# W501X.net
KiCad netlist of a schematic drawn in EAGLE
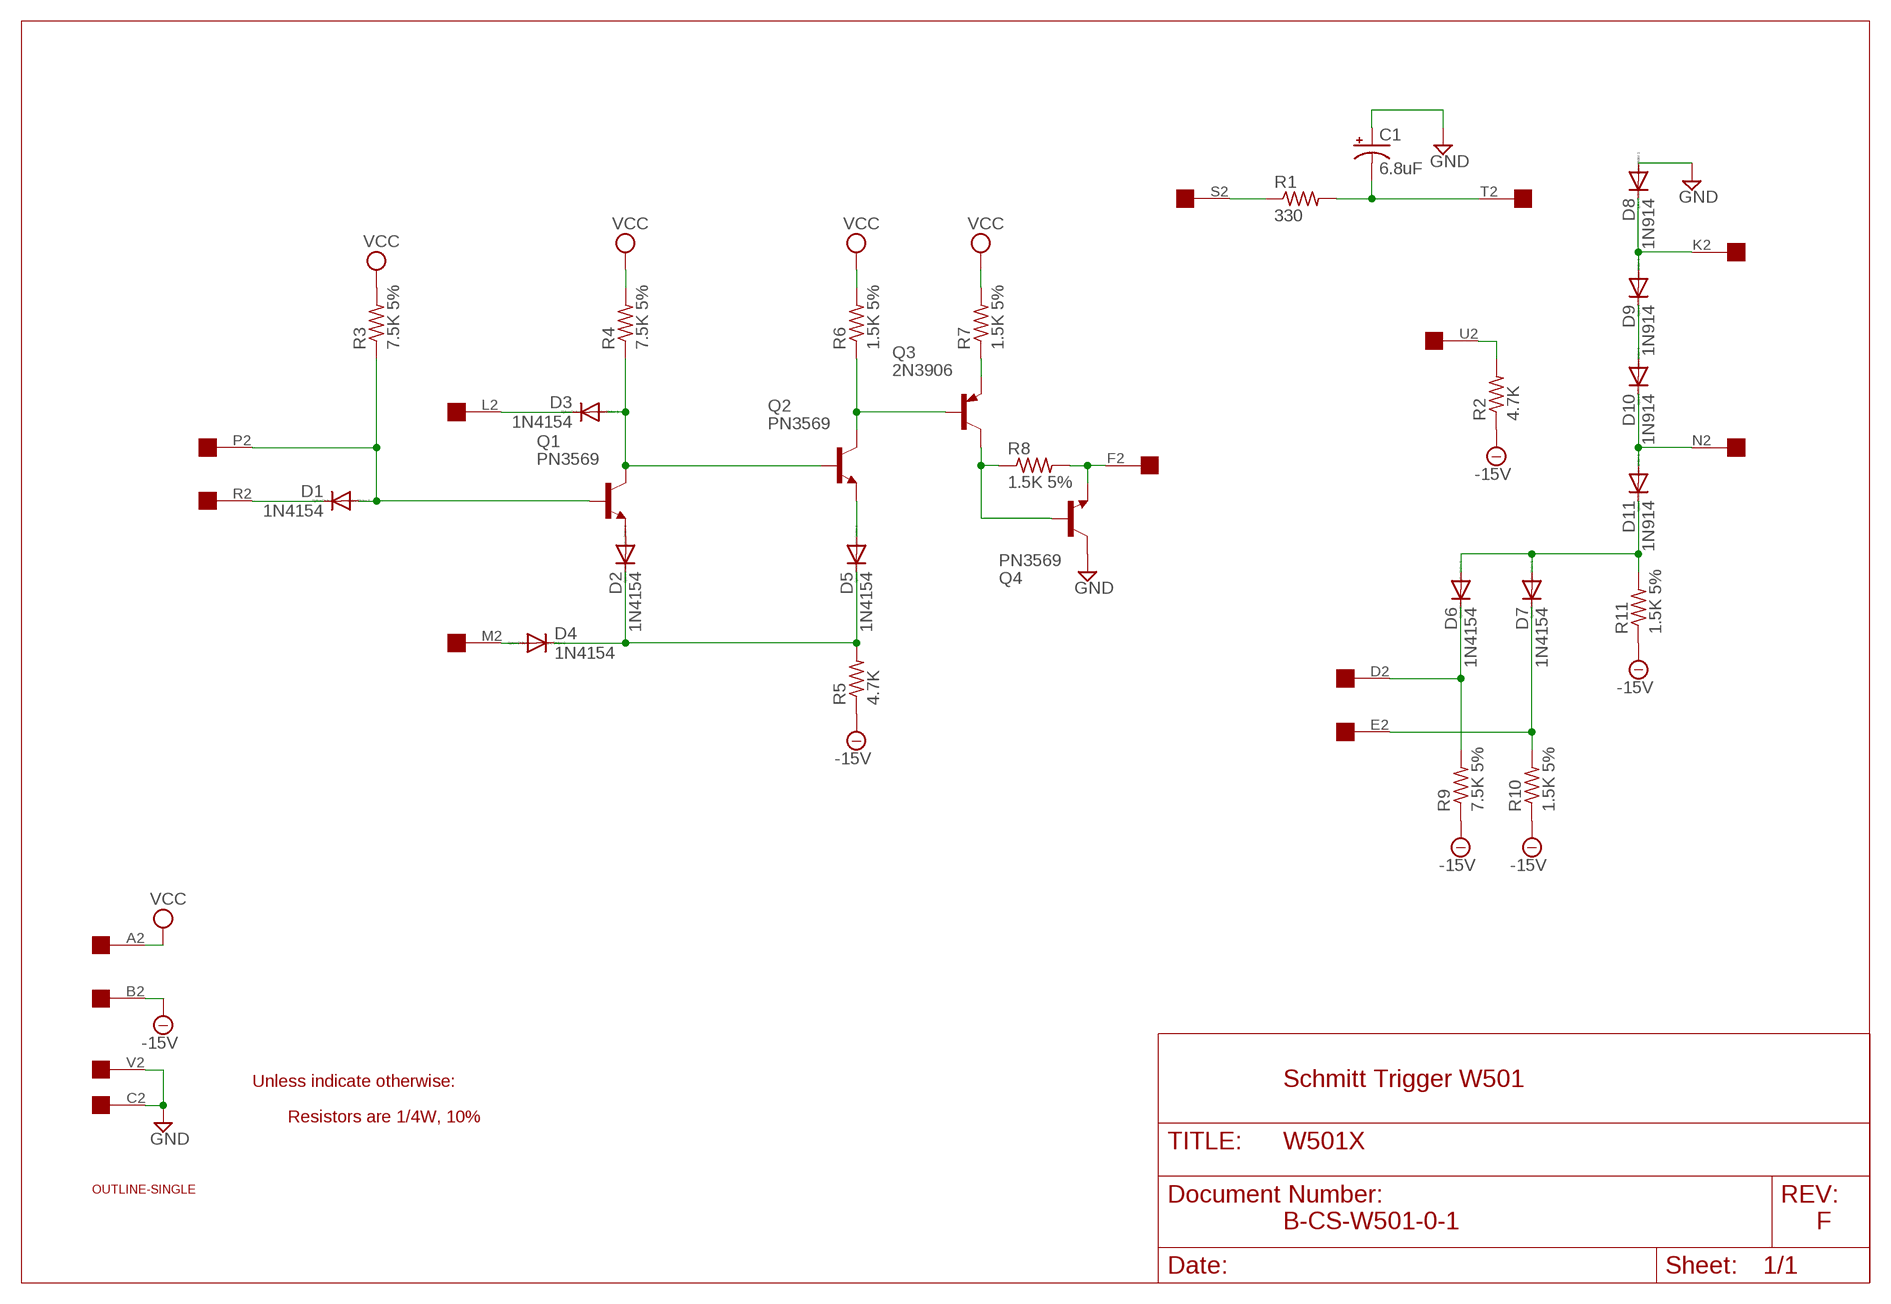
[diagram p0: schematic, sheet 1]

(export (version "E")
  (design (tool "Eeschema 10.0.6"))
  (components
    (comp (ref "C1")
      (value "6.8uF")
      (footprint "eagle-import:E15-5")
      (libsource (lib "eagle-import") (part "CPOL-USE15-5AXIAL"))
    )
    (comp (ref "D1")
      (value "1N4154")
      (footprint "eagle-import:DO35-10")
      (libsource (lib "eagle-import") (part "1N4148DO35-10"))
    )
    (comp (ref "D2")
      (value "1N4154")
      (footprint "eagle-import:DO35-10")
      (libsource (lib "eagle-import") (part "1N4148DO35-10"))
    )
    (comp (ref "D3")
      (value "1N4154")
      (footprint "eagle-import:DO35-10")
      (libsource (lib "eagle-import") (part "1N4148DO35-10"))
    )
    (comp (ref "D4")
      (value "1N4154")
      (footprint "eagle-import:DO35-10")
      (libsource (lib "eagle-import") (part "1N4148DO35-10"))
    )
    (comp (ref "D5")
      (value "1N4154")
      (footprint "eagle-import:DO35-10")
      (libsource (lib "eagle-import") (part "1N4148DO35-10"))
    )
    (comp (ref "D6")
      (value "1N4154")
      (footprint "eagle-import:DO35-10")
      (libsource (lib "eagle-import") (part "1N4148DO35-10"))
    )
    (comp (ref "D7")
      (value "1N4154")
      (footprint "eagle-import:DO35-10")
      (libsource (lib "eagle-import") (part "1N4148DO35-10"))
    )
    (comp (ref "D8")
      (value "1N914")
      (footprint "eagle-import:DO35-10")
      (libsource (lib "eagle-import") (part "1N4148DO35-10"))
    )
    (comp (ref "D9")
      (value "1N914")
      (footprint "eagle-import:DO35-10")
      (libsource (lib "eagle-import") (part "1N4148DO35-10"))
    )
    (comp (ref "D10")
      (value "1N914")
      (footprint "eagle-import:DO35-10")
      (libsource (lib "eagle-import") (part "1N4148DO35-10"))
    )
    (comp (ref "D11")
      (value "1N914")
      (footprint "eagle-import:DO35-10")
      (libsource (lib "eagle-import") (part "1N4148DO35-10"))
    )
    (comp (ref "EDGE")
      (value "EDGE-1")
      (footprint "eagle-import:EDGE-CON1")
      (libsource (lib "eagle-import") (part "EDGE-1"))
    )
    (comp (ref "Q1")
      (value "PN3569")
      (footprint "eagle-import:TO5")
      (libsource (lib "eagle-import") (part "2N2102"))
    )
    (comp (ref "Q2")
      (value "PN3569")
      (footprint "eagle-import:TO5")
      (libsource (lib "eagle-import") (part "2N2102"))
    )
    (comp (ref "Q3")
      (value "2N3906")
      (footprint "eagle-import:TO39")
      (libsource (lib "eagle-import") (part "2N2904"))
    )
    (comp (ref "Q4")
      (value "PN3569")
      (footprint "eagle-import:TO5")
      (libsource (lib "eagle-import") (part "2N2102"))
    )
    (comp (ref "R1")
      (value "330")
      (footprint "eagle-import:0207_10")
      (libsource (lib "eagle-import") (part "R-US_0207/10"))
    )
    (comp (ref "R2")
      (value "4.7K")
      (footprint "eagle-import:0207_10")
      (libsource (lib "eagle-import") (part "R-US_0207/10"))
    )
    (comp (ref "R3")
      (value "7.5K 5%")
      (footprint "eagle-import:0207_10")
      (libsource (lib "eagle-import") (part "R-US_0207/10"))
    )
    (comp (ref "R4")
      (value "7.5K 5%")
      (footprint "eagle-import:0207_10")
      (libsource (lib "eagle-import") (part "R-US_0207/10"))
    )
    (comp (ref "R5")
      (value "4.7K")
      (footprint "eagle-import:0207_10")
      (libsource (lib "eagle-import") (part "R-US_0207/10"))
    )
    (comp (ref "R6")
      (value "1.5K 5%")
      (footprint "eagle-import:0207_10")
      (libsource (lib "eagle-import") (part "R-US_0207/10"))
    )
    (comp (ref "R7")
      (value "1.5K 5%")
      (footprint "eagle-import:0207_10")
      (libsource (lib "eagle-import") (part "R-US_0207/10"))
    )
    (comp (ref "R8")
      (value "1.5K 5%")
      (footprint "eagle-import:0207_10")
      (libsource (lib "eagle-import") (part "R-US_0207/10"))
    )
    (comp (ref "R9")
      (value "7.5K 5%")
      (footprint "eagle-import:0207_10")
      (libsource (lib "eagle-import") (part "R-US_0207/10"))
    )
    (comp (ref "R10")
      (value "1.5K 5%")
      (footprint "eagle-import:0207_10")
      (libsource (lib "eagle-import") (part "R-US_0207/10"))
    )
    (comp (ref "R11")
      (value "1.5K 5%")
      (footprint "eagle-import:0207_10")
      (libsource (lib "eagle-import") (part "R-US_0207/10"))
    )
    (comp (ref "U$1")
      (value "OUTLINE-SINGLE")
      (footprint "eagle-import:SINGLE")
      (libsource (lib "eagle-import") (part "OUTLINE-SINGLE"))
    )
  )
  (nets
    (net (code "1") (name "-15V") (class "Default")
      (node (ref "EDGE") (pin "B2") (pinfunction "1_B2") (pintype "bidirectional"))
      (node (ref "R10") (pin "1") (pinfunction "1_1") (pintype "passive"))
      (node (ref "R11") (pin "1") (pinfunction "1_1") (pintype "passive"))
      (node (ref "R2") (pin "1") (pinfunction "1_1") (pintype "passive"))
      (node (ref "R5") (pin "1") (pinfunction "1_1") (pintype "passive"))
      (node (ref "R9") (pin "1") (pinfunction "1_1") (pintype "passive"))
    )
    (net (code "2") (name "GND") (class "Default")
      (node (ref "C1") (pin "+") (pinfunction "+_+") (pintype "passive"))
      (node (ref "D8") (pin "A") (pinfunction "A_A") (pintype "passive"))
      (node (ref "EDGE") (pin "C2") (pinfunction "1_C2") (pintype "bidirectional"))
      (node (ref "EDGE") (pin "V2") (pinfunction "1_V2") (pintype "bidirectional"))
      (node (ref "Q4") (pin "3") (pinfunction "C_3") (pintype "passive"))
    )
    (net (code "3") (name "Net-(D2-PadC)") (class "Default")
      (node (ref "D2") (pin "C") (pinfunction "C_C") (pintype "passive"))
      (node (ref "D4") (pin "C") (pinfunction "C_C") (pintype "passive"))
      (node (ref "D5") (pin "C") (pinfunction "C_C") (pintype "passive"))
      (node (ref "R5") (pin "2") (pinfunction "2_2") (pintype "passive"))
    )
    (net (code "4") (name "Net-(D10-PadA)") (class "Default")
      (node (ref "D10") (pin "A") (pinfunction "A_A") (pintype "passive"))
      (node (ref "D9") (pin "C") (pinfunction "C_C") (pintype "passive"))
    )
    (net (code "5") (name "Net-(D11-PadC)") (class "Default")
      (node (ref "D11") (pin "C") (pinfunction "C_C") (pintype "passive"))
      (node (ref "D6") (pin "A") (pinfunction "A_A") (pintype "passive"))
      (node (ref "D7") (pin "A") (pinfunction "A_A") (pintype "passive"))
      (node (ref "R11") (pin "2") (pinfunction "2_2") (pintype "passive"))
    )
    (net (code "6") (name "Net-(EDGED-1)") (class "Default")
      (node (ref "D6") (pin "C") (pinfunction "C_C") (pintype "passive"))
      (node (ref "EDGE") (pin "D2") (pinfunction "1_D2") (pintype "bidirectional"))
      (node (ref "R9") (pin "2") (pinfunction "2_2") (pintype "passive"))
    )
    (net (code "7") (name "Net-(EDGEE-1)") (class "Default")
      (node (ref "D7") (pin "C") (pinfunction "C_C") (pintype "passive"))
      (node (ref "EDGE") (pin "E2") (pinfunction "1_E2") (pintype "bidirectional"))
      (node (ref "R10") (pin "2") (pinfunction "2_2") (pintype "passive"))
    )
    (net (code "8") (name "Net-(EDGEF-1)") (class "Default")
      (node (ref "EDGE") (pin "F2") (pinfunction "1_F2") (pintype "bidirectional"))
      (node (ref "Q4") (pin "1") (pinfunction "E_1") (pintype "passive"))
      (node (ref "R8") (pin "2") (pinfunction "2_2") (pintype "passive"))
    )
    (net (code "9") (name "Net-(EDGEI-1)") (class "Default")
      (node (ref "D8") (pin "C") (pinfunction "C_C") (pintype "passive"))
      (node (ref "D9") (pin "A") (pinfunction "A_A") (pintype "passive"))
      (node (ref "EDGE") (pin "K2") (pinfunction "1_K2") (pintype "bidirectional"))
    )
    (net (code "10") (name "Net-(EDGEJ-1)") (class "Default")
      (node (ref "D3") (pin "C") (pinfunction "C_C") (pintype "passive"))
      (node (ref "EDGE") (pin "L2") (pinfunction "1_L2") (pintype "bidirectional"))
    )
    (net (code "11") (name "Net-(EDGEK-1)") (class "Default")
      (node (ref "D4") (pin "A") (pinfunction "A_A") (pintype "passive"))
      (node (ref "EDGE") (pin "M2") (pinfunction "1_M2") (pintype "bidirectional"))
    )
    (net (code "12") (name "Net-(EDGEL-1)") (class "Default")
      (node (ref "D10") (pin "C") (pinfunction "C_C") (pintype "passive"))
      (node (ref "D11") (pin "A") (pinfunction "A_A") (pintype "passive"))
      (node (ref "EDGE") (pin "N2") (pinfunction "1_N2") (pintype "bidirectional"))
    )
    (net (code "13") (name "Net-(EDGEM-1)") (class "Default")
      (node (ref "D1") (pin "A") (pinfunction "A_A") (pintype "passive"))
      (node (ref "EDGE") (pin "P2") (pinfunction "1_P2") (pintype "bidirectional"))
      (node (ref "Q1") (pin "2") (pinfunction "B_2") (pintype "passive"))
      (node (ref "R3") (pin "1") (pinfunction "1_1") (pintype "passive"))
    )
    (net (code "14") (name "Net-(EDGEN-1)") (class "Default")
      (node (ref "D1") (pin "C") (pinfunction "C_C") (pintype "passive"))
      (node (ref "EDGE") (pin "R2") (pinfunction "1_R2") (pintype "bidirectional"))
    )
    (net (code "15") (name "Net-(EDGEO-1)") (class "Default")
      (node (ref "EDGE") (pin "S2") (pinfunction "1_S2") (pintype "bidirectional"))
      (node (ref "R1") (pin "1") (pinfunction "1_1") (pintype "passive"))
    )
    (net (code "16") (name "Net-(EDGEP-1)") (class "Default")
      (node (ref "C1") (pin "-") (pinfunction "-_-") (pintype "passive"))
      (node (ref "EDGE") (pin "T2") (pinfunction "1_T2") (pintype "bidirectional"))
      (node (ref "R1") (pin "2") (pinfunction "2_2") (pintype "passive"))
    )
    (net (code "17") (name "Net-(EDGEQ-1)") (class "Default")
      (node (ref "EDGE") (pin "U2") (pinfunction "1_U2") (pintype "bidirectional"))
      (node (ref "R2") (pin "2") (pinfunction "2_2") (pintype "passive"))
    )
    (net (code "18") (name "Net-(Q1-C)") (class "Default")
      (node (ref "D3") (pin "A") (pinfunction "A_A") (pintype "passive"))
      (node (ref "Q1") (pin "3") (pinfunction "C_3") (pintype "passive"))
      (node (ref "Q2") (pin "2") (pinfunction "B_2") (pintype "passive"))
      (node (ref "R4") (pin "1") (pinfunction "1_1") (pintype "passive"))
    )
    (net (code "19") (name "Net-(Q1-E)") (class "Default")
      (node (ref "D2") (pin "A") (pinfunction "A_A") (pintype "passive"))
      (node (ref "Q1") (pin "1") (pinfunction "E_1") (pintype "passive"))
    )
    (net (code "20") (name "Net-(Q2-C)") (class "Default")
      (node (ref "Q2") (pin "3") (pinfunction "C_3") (pintype "passive"))
      (node (ref "Q3") (pin "2") (pinfunction "B_2") (pintype "passive"))
      (node (ref "R6") (pin "1") (pinfunction "1_1") (pintype "passive"))
    )
    (net (code "21") (name "Net-(Q2-E)") (class "Default")
      (node (ref "D5") (pin "A") (pinfunction "A_A") (pintype "passive"))
      (node (ref "Q2") (pin "1") (pinfunction "E_1") (pintype "passive"))
    )
    (net (code "22") (name "Net-(Q3-C)") (class "Default")
      (node (ref "Q3") (pin "3") (pinfunction "C_3") (pintype "passive"))
      (node (ref "Q4") (pin "2") (pinfunction "B_2") (pintype "passive"))
      (node (ref "R8") (pin "1") (pinfunction "1_1") (pintype "passive"))
    )
    (net (code "23") (name "Net-(Q3-E)") (class "Default")
      (node (ref "Q3") (pin "1") (pinfunction "E_1") (pintype "passive"))
      (node (ref "R7") (pin "1") (pinfunction "1_1") (pintype "passive"))
    )
    (net (code "24") (name "VCC") (class "Default")
      (node (ref "EDGE") (pin "A2") (pinfunction "1_A2") (pintype "bidirectional"))
      (node (ref "R3") (pin "2") (pinfunction "2_2") (pintype "passive"))
      (node (ref "R4") (pin "2") (pinfunction "2_2") (pintype "passive"))
      (node (ref "R6") (pin "2") (pinfunction "2_2") (pintype "passive"))
      (node (ref "R7") (pin "2") (pinfunction "2_2") (pintype "passive"))
    )
  )
)
